# PCB__STM32_APDS9960.net
KiCad netlist of a schematic drawn in EAGLE
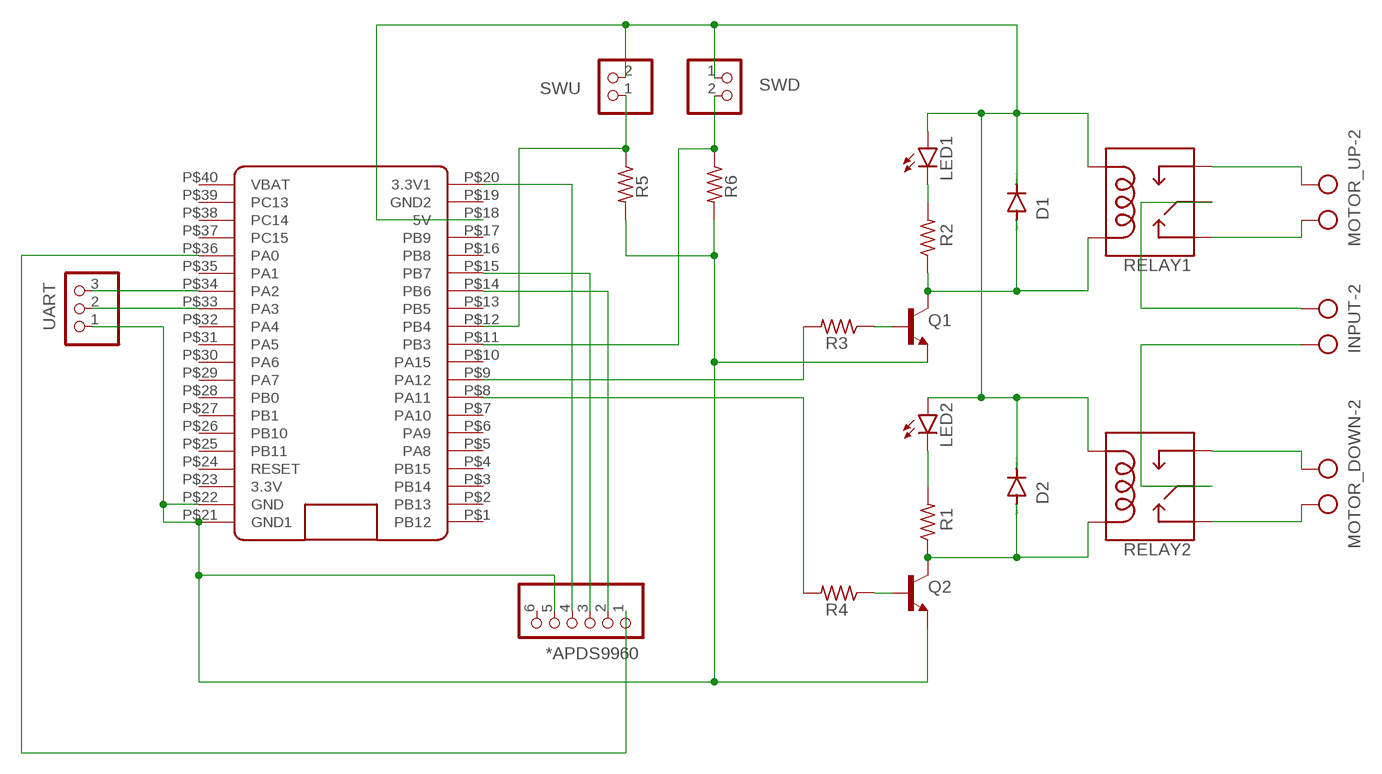
[diagram p0: schematic, sheet 1]

(export (version "E")
  (design (tool "Eeschema 10.0.6"))
  (components
    (comp (ref "*APDS9960")
      (value "PINHD-1X6")
      (footprint "eagle-import:1X06")
      (libsource (lib "eagle-import") (part "PINHD-1X6"))
    )
    (comp (ref "D1")
      (value "1N4446")
      (footprint "eagle-import:DO35-10")
      (libsource (lib "eagle-import") (part "1N4446"))
    )
    (comp (ref "D2")
      (value "1N4446")
      (footprint "eagle-import:DO35-10")
      (libsource (lib "eagle-import") (part "1N4446"))
    )
    (comp (ref "INPUT")
      (value "AK500/2")
      (footprint "eagle-import:AK500_2")
      (libsource (lib "eagle-import") (part "AK500/2"))
    )
    (comp (ref "LED1")
      (value "TLLR4400")
      (footprint "eagle-import:LED3MM")
      (fields (field (name "MF") "VISHAY SEMICONDUCTOR"))
      (libsource (lib "eagle-import") (part "TLLR4400"))
    )
    (comp (ref "LED2")
      (value "TLLR4400")
      (footprint "eagle-import:LED3MM")
      (fields (field (name "MF") "VISHAY SEMICONDUCTOR"))
      (libsource (lib "eagle-import") (part "TLLR4400"))
    )
    (comp (ref "MOTOR_DOWN")
      (value "AK500/2")
      (footprint "eagle-import:AK500_2")
      (libsource (lib "eagle-import") (part "AK500/2"))
    )
    (comp (ref "MOTOR_UP")
      (value "AK500/2")
      (footprint "eagle-import:AK500_2")
      (libsource (lib "eagle-import") (part "AK500/2"))
    )
    (comp (ref "Q1")
      (value "2N3904")
      (footprint "eagle-import:TO92")
      (libsource (lib "eagle-import") (part "2N3904"))
    )
    (comp (ref "Q2")
      (value "2N3904")
      (footprint "eagle-import:TO92")
      (libsource (lib "eagle-import") (part "2N3904"))
    )
    (comp (ref "R1")
      (value "R-US_0207/10")
      (footprint "eagle-import:0207_10")
      (libsource (lib "eagle-import") (part "R-US_0207/10"))
    )
    (comp (ref "R2")
      (value "R-US_0207/10")
      (footprint "eagle-import:0207_10")
      (libsource (lib "eagle-import") (part "R-US_0207/10"))
    )
    (comp (ref "R3")
      (value "R-US_0207/10")
      (footprint "eagle-import:0207_10")
      (libsource (lib "eagle-import") (part "R-US_0207/10"))
    )
    (comp (ref "R4")
      (value "R-US_0207/10")
      (footprint "eagle-import:0207_10")
      (libsource (lib "eagle-import") (part "R-US_0207/10"))
    )
    (comp (ref "R5")
      (value "R-US_0207/10")
      (footprint "eagle-import:0207_10")
      (libsource (lib "eagle-import") (part "R-US_0207/10"))
    )
    (comp (ref "R6")
      (value "R-US_0207/10")
      (footprint "eagle-import:0207_10")
      (libsource (lib "eagle-import") (part "R-US_0207/10"))
    )
    (comp (ref "RELAY1")
      (value "RELAYPTH")
      (footprint "eagle-import:SRD-05VDC-SL-C")
      (libsource (lib "eagle-import") (part "RELAYPTH"))
    )
    (comp (ref "RELAY2")
      (value "RELAYPTH")
      (footprint "eagle-import:SRD-05VDC-SL-C")
      (libsource (lib "eagle-import") (part "RELAYPTH"))
    )
    (comp (ref "SWD")
      (value "PINHD-1X2")
      (footprint "eagle-import:1X02")
      (libsource (lib "eagle-import") (part "PINHD-1X2"))
    )
    (comp (ref "SWU")
      (value "PINHD-1X2")
      (footprint "eagle-import:1X02")
      (libsource (lib "eagle-import") (part "PINHD-1X2"))
    )
    (comp (ref "U$1")
      (value "BLUE_PILL")
      (footprint "eagle-import:BLUE_PILL")
      (libsource (lib "eagle-import") (part "BLUE_PILL"))
    )
    (comp (ref "UART")
      (value "PINHD-1X3")
      (footprint "eagle-import:1X03")
      (libsource (lib "eagle-import") (part "PINHD-1X3"))
    )
  )
  (nets
    (net (code "1") (name "Net-(INPUTA-KL)") (class "Default")
      (node (ref "INPUT") (pin "1") (pinfunction "KL_1") (pintype "passive"))
      (node (ref "RELAY2") (pin "SWCOMMON") (pinfunction "SWCOMMON_SWCOMMON") (pintype "bidirectional"))
    )
    (net (code "2") (name "Net-(INPUTB-KL)") (class "Default")
      (node (ref "INPUT") (pin "2") (pinfunction "KL_2") (pintype "passive"))
      (node (ref "RELAY1") (pin "SWCOMMON") (pinfunction "SWCOMMON_SWCOMMON") (pintype "bidirectional"))
    )
    (net (code "3") (name "Net-(LED1-C)") (class "Default")
      (node (ref "LED1") (pin "K") (pinfunction "C_K") (pintype "passive"))
      (node (ref "R2") (pin "2") (pinfunction "2_2") (pintype "passive"))
    )
    (net (code "4") (name "Net-(LED2-C)") (class "Default")
      (node (ref "LED2") (pin "K") (pinfunction "C_K") (pintype "passive"))
      (node (ref "R1") (pin "2") (pinfunction "2_2") (pintype "passive"))
    )
    (net (code "5") (name "Net-(MOTOR_DOWNA-KL)") (class "Default")
      (node (ref "MOTOR_DOWN") (pin "1") (pinfunction "KL_1") (pintype "passive"))
      (node (ref "RELAY2") (pin "SWCLOSED") (pinfunction "SWCLOSE_SWCLOSED") (pintype "bidirectional"))
    )
    (net (code "6") (name "Net-(MOTOR_DOWNB-KL)") (class "Default")
      (node (ref "MOTOR_DOWN") (pin "2") (pinfunction "KL_2") (pintype "passive"))
      (node (ref "RELAY2") (pin "SWOPEN") (pinfunction "SWOPEN_SWOPEN") (pintype "bidirectional"))
    )
    (net (code "7") (name "Net-(MOTOR_UPA-KL)") (class "Default")
      (node (ref "MOTOR_UP") (pin "1") (pinfunction "KL_1") (pintype "passive"))
      (node (ref "RELAY1") (pin "SWCLOSED") (pinfunction "SWCLOSE_SWCLOSED") (pintype "bidirectional"))
    )
    (net (code "8") (name "Net-(MOTOR_UPB-KL)") (class "Default")
      (node (ref "MOTOR_UP") (pin "2") (pinfunction "KL_2") (pintype "passive"))
      (node (ref "RELAY1") (pin "SWOPEN") (pinfunction "SWOPEN_SWOPEN") (pintype "bidirectional"))
    )
    (net (code "9") (name "Net-(Q1-B)") (class "Default")
      (node (ref "Q1") (pin "2") (pinfunction "B_2") (pintype "passive"))
      (node (ref "R3") (pin "1") (pinfunction "1_1") (pintype "passive"))
    )
    (net (code "10") (name "Net-(Q1-C)") (class "Default")
      (node (ref "D1") (pin "A") (pinfunction "A_A") (pintype "passive"))
      (node (ref "Q1") (pin "1") (pinfunction "C_1") (pintype "passive"))
      (node (ref "R2") (pin "1") (pinfunction "1_1") (pintype "passive"))
      (node (ref "RELAY1") (pin "COIL1") (pinfunction "COIL1_COIL1") (pintype "bidirectional"))
    )
    (net (code "11") (name "Net-(Q1-E)") (class "Default")
      (node (ref "*APDS9960") (pin "5") (pinfunction "5_5") (pintype "passive"))
      (node (ref "Q1") (pin "3") (pinfunction "E_3") (pintype "passive"))
      (node (ref "Q2") (pin "3") (pinfunction "E_3") (pintype "passive"))
      (node (ref "R5") (pin "2") (pinfunction "2_2") (pintype "passive"))
      (node (ref "R6") (pin "2") (pinfunction "2_2") (pintype "passive"))
      (node (ref "U$1") (pin "P$21") (pinfunction "GND1_P$21") (pintype "power_in"))
      (node (ref "U$1") (pin "P$22") (pinfunction "GND_P$22") (pintype "bidirectional"))
      (node (ref "UART") (pin "1") (pinfunction "1_1") (pintype "passive"))
    )
    (net (code "12") (name "Net-(Q2-B)") (class "Default")
      (node (ref "Q2") (pin "2") (pinfunction "B_2") (pintype "passive"))
      (node (ref "R4") (pin "1") (pinfunction "1_1") (pintype "passive"))
    )
    (net (code "13") (name "Net-(Q2-C)") (class "Default")
      (node (ref "D2") (pin "A") (pinfunction "A_A") (pintype "passive"))
      (node (ref "Q2") (pin "1") (pinfunction "C_1") (pintype "passive"))
      (node (ref "R1") (pin "1") (pinfunction "1_1") (pintype "passive"))
      (node (ref "RELAY2") (pin "COIL1") (pinfunction "COIL1_COIL1") (pintype "bidirectional"))
    )
    (net (code "14") (name "Net-(U$1-3.3V1)") (class "Default")
      (node (ref "*APDS9960") (pin "4") (pinfunction "4_4") (pintype "passive"))
      (node (ref "U$1") (pin "P$20") (pinfunction "3.3V1_P$20") (pintype "bidirectional"))
    )
    (net (code "15") (name "Net-(U$1-5V)") (class "Default")
      (node (ref "D1") (pin "C") (pinfunction "C_C") (pintype "passive"))
      (node (ref "D2") (pin "C") (pinfunction "C_C") (pintype "passive"))
      (node (ref "LED1") (pin "A") (pinfunction "A_A") (pintype "passive"))
      (node (ref "LED2") (pin "A") (pinfunction "A_A") (pintype "passive"))
      (node (ref "RELAY1") (pin "COIL0") (pinfunction "COIL0_COIL0") (pintype "bidirectional"))
      (node (ref "RELAY2") (pin "COIL0") (pinfunction "COIL0_COIL0") (pintype "bidirectional"))
      (node (ref "SWD") (pin "1") (pinfunction "1_1") (pintype "passive"))
      (node (ref "SWU") (pin "2") (pinfunction "2_2") (pintype "passive"))
      (node (ref "U$1") (pin "P$18") (pinfunction "5V_P$18") (pintype "bidirectional"))
    )
    (net (code "16") (name "Net-(U$1-PA0)") (class "Default")
      (node (ref "*APDS9960") (pin "1") (pinfunction "1_1") (pintype "passive"))
      (node (ref "U$1") (pin "P$36") (pinfunction "PA0_P$36") (pintype "bidirectional"))
    )
    (net (code "17") (name "Net-(U$1-PA2)") (class "Default")
      (node (ref "U$1") (pin "P$34") (pinfunction "PA2_P$34") (pintype "bidirectional"))
      (node (ref "UART") (pin "3") (pinfunction "3_3") (pintype "passive"))
    )
    (net (code "18") (name "Net-(U$1-PA3)") (class "Default")
      (node (ref "U$1") (pin "P$33") (pinfunction "PA3_P$33") (pintype "bidirectional"))
      (node (ref "UART") (pin "2") (pinfunction "2_2") (pintype "passive"))
    )
    (net (code "19") (name "Net-(U$1-PA11)") (class "Default")
      (node (ref "R4") (pin "2") (pinfunction "2_2") (pintype "passive"))
      (node (ref "U$1") (pin "P$8") (pinfunction "PA11_P$8") (pintype "bidirectional"))
    )
    (net (code "20") (name "Net-(U$1-PA12)") (class "Default")
      (node (ref "R3") (pin "2") (pinfunction "2_2") (pintype "passive"))
      (node (ref "U$1") (pin "P$9") (pinfunction "PA12_P$9") (pintype "bidirectional"))
    )
    (net (code "21") (name "Net-(U$1-PB3)") (class "Default")
      (node (ref "R6") (pin "1") (pinfunction "1_1") (pintype "passive"))
      (node (ref "SWD") (pin "2") (pinfunction "2_2") (pintype "passive"))
      (node (ref "U$1") (pin "P$11") (pinfunction "PB3_P$11") (pintype "bidirectional"))
    )
    (net (code "22") (name "Net-(U$1-PB4)") (class "Default")
      (node (ref "R5") (pin "1") (pinfunction "1_1") (pintype "passive"))
      (node (ref "SWU") (pin "1") (pinfunction "1_1") (pintype "passive"))
      (node (ref "U$1") (pin "P$12") (pinfunction "PB4_P$12") (pintype "bidirectional"))
    )
    (net (code "23") (name "Net-(U$1-PB6)") (class "Default")
      (node (ref "*APDS9960") (pin "2") (pinfunction "2_2") (pintype "passive"))
      (node (ref "U$1") (pin "P$14") (pinfunction "PB6_P$14") (pintype "bidirectional"))
    )
    (net (code "24") (name "Net-(U$1-PB7)") (class "Default")
      (node (ref "*APDS9960") (pin "3") (pinfunction "3_3") (pintype "passive"))
      (node (ref "U$1") (pin "P$15") (pinfunction "PB7_P$15") (pintype "bidirectional"))
    )
    (net (code "25") (name "unconnected-(*APDS9960-Pad6)") (class "Default")
      (node (ref "*APDS9960") (pin "6") (pinfunction "6_6") (pintype "passive"))
    )
    (net (code "26") (name "unconnected-(U$1-3.3V-PadP$23)") (class "Default")
      (node (ref "U$1") (pin "P$23") (pinfunction "3.3V_P$23") (pintype "bidirectional"))
    )
    (net (code "27") (name "unconnected-(U$1-GND2-PadP$19)") (class "Default")
      (node (ref "U$1") (pin "P$19") (pinfunction "GND2_P$19") (pintype "bidirectional"))
    )
    (net (code "28") (name "unconnected-(U$1-PA1-PadP$35)") (class "Default")
      (node (ref "U$1") (pin "P$35") (pinfunction "PA1_P$35") (pintype "bidirectional"))
    )
    (net (code "29") (name "unconnected-(U$1-PA4-PadP$32)") (class "Default")
      (node (ref "U$1") (pin "P$32") (pinfunction "PA4_P$32") (pintype "bidirectional"))
    )
    (net (code "30") (name "unconnected-(U$1-PA5-PadP$31)") (class "Default")
      (node (ref "U$1") (pin "P$31") (pinfunction "PA5_P$31") (pintype "bidirectional"))
    )
    (net (code "31") (name "unconnected-(U$1-PA6-PadP$30)") (class "Default")
      (node (ref "U$1") (pin "P$30") (pinfunction "PA6_P$30") (pintype "bidirectional"))
    )
    (net (code "32") (name "unconnected-(U$1-PA7-PadP$29)") (class "Default")
      (node (ref "U$1") (pin "P$29") (pinfunction "PA7_P$29") (pintype "bidirectional"))
    )
    (net (code "33") (name "unconnected-(U$1-PA8-PadP$5)") (class "Default")
      (node (ref "U$1") (pin "P$5") (pinfunction "PA8_P$5") (pintype "bidirectional"))
    )
    (net (code "34") (name "unconnected-(U$1-PA9-PadP$6)") (class "Default")
      (node (ref "U$1") (pin "P$6") (pinfunction "PA9_P$6") (pintype "bidirectional"))
    )
    (net (code "35") (name "unconnected-(U$1-PA10-PadP$7)") (class "Default")
      (node (ref "U$1") (pin "P$7") (pinfunction "PA10_P$7") (pintype "bidirectional"))
    )
    (net (code "36") (name "unconnected-(U$1-PA15-PadP$10)") (class "Default")
      (node (ref "U$1") (pin "P$10") (pinfunction "PA15_P$10") (pintype "bidirectional"))
    )
    (net (code "37") (name "unconnected-(U$1-PB0-PadP$28)") (class "Default")
      (node (ref "U$1") (pin "P$28") (pinfunction "PB0_P$28") (pintype "bidirectional"))
    )
    (net (code "38") (name "unconnected-(U$1-PB1-PadP$27)") (class "Default")
      (node (ref "U$1") (pin "P$27") (pinfunction "PB1_P$27") (pintype "bidirectional"))
    )
    (net (code "39") (name "unconnected-(U$1-PB5-PadP$13)") (class "Default")
      (node (ref "U$1") (pin "P$13") (pinfunction "PB5_P$13") (pintype "bidirectional"))
    )
    (net (code "40") (name "unconnected-(U$1-PB8-PadP$16)") (class "Default")
      (node (ref "U$1") (pin "P$16") (pinfunction "PB8_P$16") (pintype "bidirectional"))
    )
    (net (code "41") (name "unconnected-(U$1-PB9-PadP$17)") (class "Default")
      (node (ref "U$1") (pin "P$17") (pinfunction "PB9_P$17") (pintype "bidirectional"))
    )
    (net (code "42") (name "unconnected-(U$1-PB10-PadP$26)") (class "Default")
      (node (ref "U$1") (pin "P$26") (pinfunction "PB10_P$26") (pintype "bidirectional"))
    )
    (net (code "43") (name "unconnected-(U$1-PB11-PadP$25)") (class "Default")
      (node (ref "U$1") (pin "P$25") (pinfunction "PB11_P$25") (pintype "bidirectional"))
    )
    (net (code "44") (name "unconnected-(U$1-PB12-PadP$1)") (class "Default")
      (node (ref "U$1") (pin "P$1") (pinfunction "PB12_P$1") (pintype "bidirectional"))
    )
    (net (code "45") (name "unconnected-(U$1-PB13-PadP$2)") (class "Default")
      (node (ref "U$1") (pin "P$2") (pinfunction "PB13_P$2") (pintype "bidirectional"))
    )
    (net (code "46") (name "unconnected-(U$1-PB14-PadP$3)") (class "Default")
      (node (ref "U$1") (pin "P$3") (pinfunction "PB14_P$3") (pintype "bidirectional"))
    )
    (net (code "47") (name "unconnected-(U$1-PB15-PadP$4)") (class "Default")
      (node (ref "U$1") (pin "P$4") (pinfunction "PB15_P$4") (pintype "bidirectional"))
    )
    (net (code "48") (name "unconnected-(U$1-PC13-PadP$39)") (class "Default")
      (node (ref "U$1") (pin "P$39") (pinfunction "PC13_P$39") (pintype "bidirectional"))
    )
    (net (code "49") (name "unconnected-(U$1-PC14-PadP$38)") (class "Default")
      (node (ref "U$1") (pin "P$38") (pinfunction "PC14_P$38") (pintype "bidirectional"))
    )
    (net (code "50") (name "unconnected-(U$1-PC15-PadP$37)") (class "Default")
      (node (ref "U$1") (pin "P$37") (pinfunction "PC15_P$37") (pintype "bidirectional"))
    )
    (net (code "51") (name "unconnected-(U$1-RESET-PadP$24)") (class "Default")
      (node (ref "U$1") (pin "P$24") (pinfunction "RESET_P$24") (pintype "bidirectional"))
    )
    (net (code "52") (name "unconnected-(U$1-VBAT-PadP$40)") (class "Default")
      (node (ref "U$1") (pin "P$40") (pinfunction "VBAT_P$40") (pintype "bidirectional"))
    )
  )
)
